# BQ2970_circuit.net
KiCad netlist of a schematic drawn in EAGLE
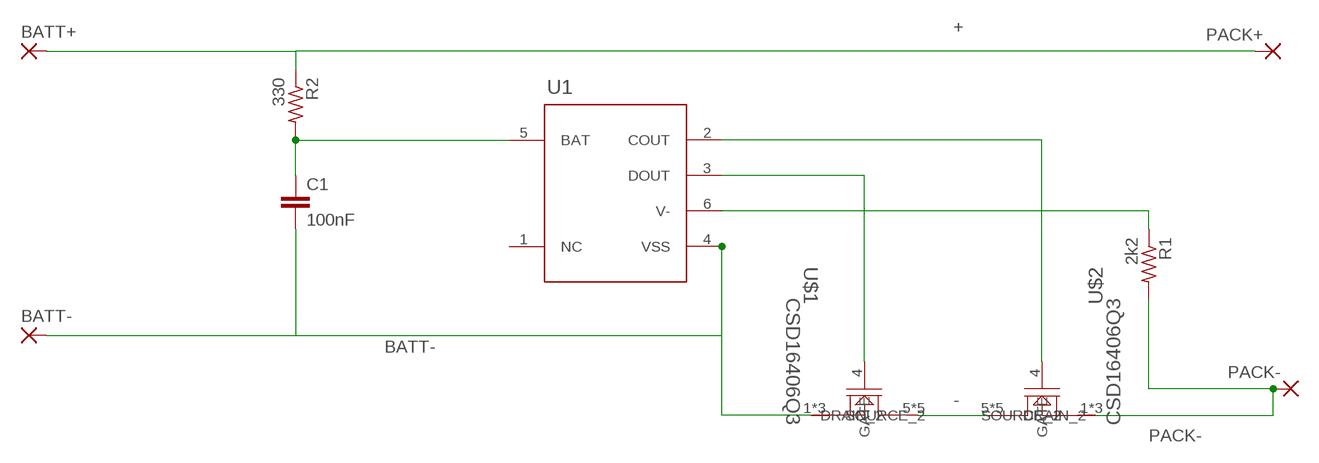
[diagram p0: schematic, sheet 1]

(export (version "E")
  (design (tool "Eeschema 10.0.6"))
  (components
    (comp (ref "BATT+")
      (value "SMD5")
      (footprint "eagle-import:SMD2,54-5,08")
      (libsource (lib "eagle-import") (part "SMD5"))
    )
    (comp (ref "BATT-")
      (value "SMD5")
      (footprint "eagle-import:SMD2,54-5,08")
      (libsource (lib "eagle-import") (part "SMD5"))
    )
    (comp (ref "C1")
      (value "100nF")
      (footprint "eagle-import:C0805")
      (libsource (lib "eagle-import") (part "C-EUC0805"))
    )
    (comp (ref "PACK+")
      (value "SMD5")
      (footprint "eagle-import:SMD2,54-5,08")
      (libsource (lib "eagle-import") (part "SMD5"))
    )
    (comp (ref "PACK-")
      (value "SMD5")
      (footprint "eagle-import:SMD2,54-5,08")
      (libsource (lib "eagle-import") (part "SMD5"))
    )
    (comp (ref "R1")
      (value "2k2")
      (footprint "eagle-import:R0805")
      (libsource (lib "eagle-import") (part "R-US_R0805"))
    )
    (comp (ref "R2")
      (value "330")
      (footprint "eagle-import:R0805")
      (libsource (lib "eagle-import") (part "R-US_R0805"))
    )
    (comp (ref "U$1")
      (value "CSD16406Q3")
      (footprint "eagle-import:DQG0008A")
      (libsource (lib "eagle-import") (part "CSD16406Q3"))
    )
    (comp (ref "U$2")
      (value "CSD16406Q3")
      (footprint "eagle-import:DQG0008A")
      (libsource (lib "eagle-import") (part "CSD16406Q3"))
    )
    (comp (ref "U1")
      (value "Value")
      (footprint "eagle-import:DSE0006A")
      (fields (field (name "MANUFACTURER") "Texas Instruments") (field (name "PARTNUMBER") "BQ29705DSER"))
      (libsource (lib "eagle-import") (part "BQ29700DSER"))
    )
  )
  (nets
    (net (code "1") (name "/+") (class "Default")
      (node (ref "BATT+") (pin "1") (pinfunction "P_1") (pintype "passive"))
      (node (ref "PACK+") (pin "1") (pinfunction "P_1") (pintype "passive"))
      (node (ref "R2") (pin "1") (pinfunction "1_1") (pintype "passive"))
    )
    (net (code "2") (name "/-") (class "Default")
      (node (ref "U$1") (pin "5") (pinfunction "DRAIN_2_5") (pintype "passive"))
      (node (ref "U$1") (pin "6") (pinfunction "DRAIN_2_6") (pintype "passive"))
      (node (ref "U$1") (pin "7") (pinfunction "DRAIN_2_7") (pintype "passive"))
      (node (ref "U$1") (pin "8") (pinfunction "DRAIN_2_8") (pintype "passive"))
      (node (ref "U$1") (pin "9") (pinfunction "DRAIN_2_9") (pintype "passive"))
      (node (ref "U$2") (pin "5") (pinfunction "DRAIN_2_5") (pintype "passive"))
      (node (ref "U$2") (pin "6") (pinfunction "DRAIN_2_6") (pintype "passive"))
      (node (ref "U$2") (pin "7") (pinfunction "DRAIN_2_7") (pintype "passive"))
      (node (ref "U$2") (pin "8") (pinfunction "DRAIN_2_8") (pintype "passive"))
      (node (ref "U$2") (pin "9") (pinfunction "DRAIN_2_9") (pintype "passive"))
    )
    (net (code "3") (name "/BATT-") (class "Default")
      (node (ref "BATT-") (pin "1") (pinfunction "P_1") (pintype "passive"))
      (node (ref "C1") (pin "2") (pinfunction "2_2") (pintype "passive"))
      (node (ref "U$1") (pin "1") (pinfunction "SOURCE_2_1") (pintype "passive"))
      (node (ref "U$1") (pin "2") (pinfunction "SOURCE_2_2") (pintype "passive"))
      (node (ref "U$1") (pin "3") (pinfunction "SOURCE_2_3") (pintype "passive"))
      (node (ref "U1") (pin "4") (pinfunction "VSS_4") (pintype "power_in"))
    )
    (net (code "4") (name "/PACK-") (class "Default")
      (node (ref "PACK-") (pin "1") (pinfunction "P_1") (pintype "passive"))
      (node (ref "R1") (pin "2") (pinfunction "2_2") (pintype "passive"))
      (node (ref "U$2") (pin "1") (pinfunction "SOURCE_2_1") (pintype "passive"))
      (node (ref "U$2") (pin "2") (pinfunction "SOURCE_2_2") (pintype "passive"))
      (node (ref "U$2") (pin "3") (pinfunction "SOURCE_2_3") (pintype "passive"))
    )
    (net (code "5") (name "Net-(U$1-GATE)") (class "Default")
      (node (ref "U$1") (pin "4") (pinfunction "GATE_4") (pintype "passive"))
      (node (ref "U1") (pin "3") (pinfunction "DOUT_3") (pintype "output"))
    )
    (net (code "6") (name "Net-(U$2-GATE)") (class "Default")
      (node (ref "U$2") (pin "4") (pinfunction "GATE_4") (pintype "passive"))
      (node (ref "U1") (pin "2") (pinfunction "COUT_2") (pintype "output"))
    )
    (net (code "7") (name "Net-(U1-BAT)") (class "Default")
      (node (ref "C1") (pin "1") (pinfunction "1_1") (pintype "passive"))
      (node (ref "R2") (pin "2") (pinfunction "2_2") (pintype "passive"))
      (node (ref "U1") (pin "5") (pinfunction "BAT_5") (pintype "power_in"))
    )
    (net (code "8") (name "Net-(U1-V-)") (class "Default")
      (node (ref "R1") (pin "1") (pinfunction "1_1") (pintype "passive"))
      (node (ref "U1") (pin "6") (pinfunction "V-_6") (pintype "bidirectional"))
    )
    (net (code "9") (name "unconnected-(U1-NC-Pad1)") (class "Default")
      (node (ref "U1") (pin "1") (pinfunction "NC_1") (pintype "passive"))
    )
  )
)
